# Tx_ckt_1.net
KiCad netlist of a schematic drawn in EAGLE
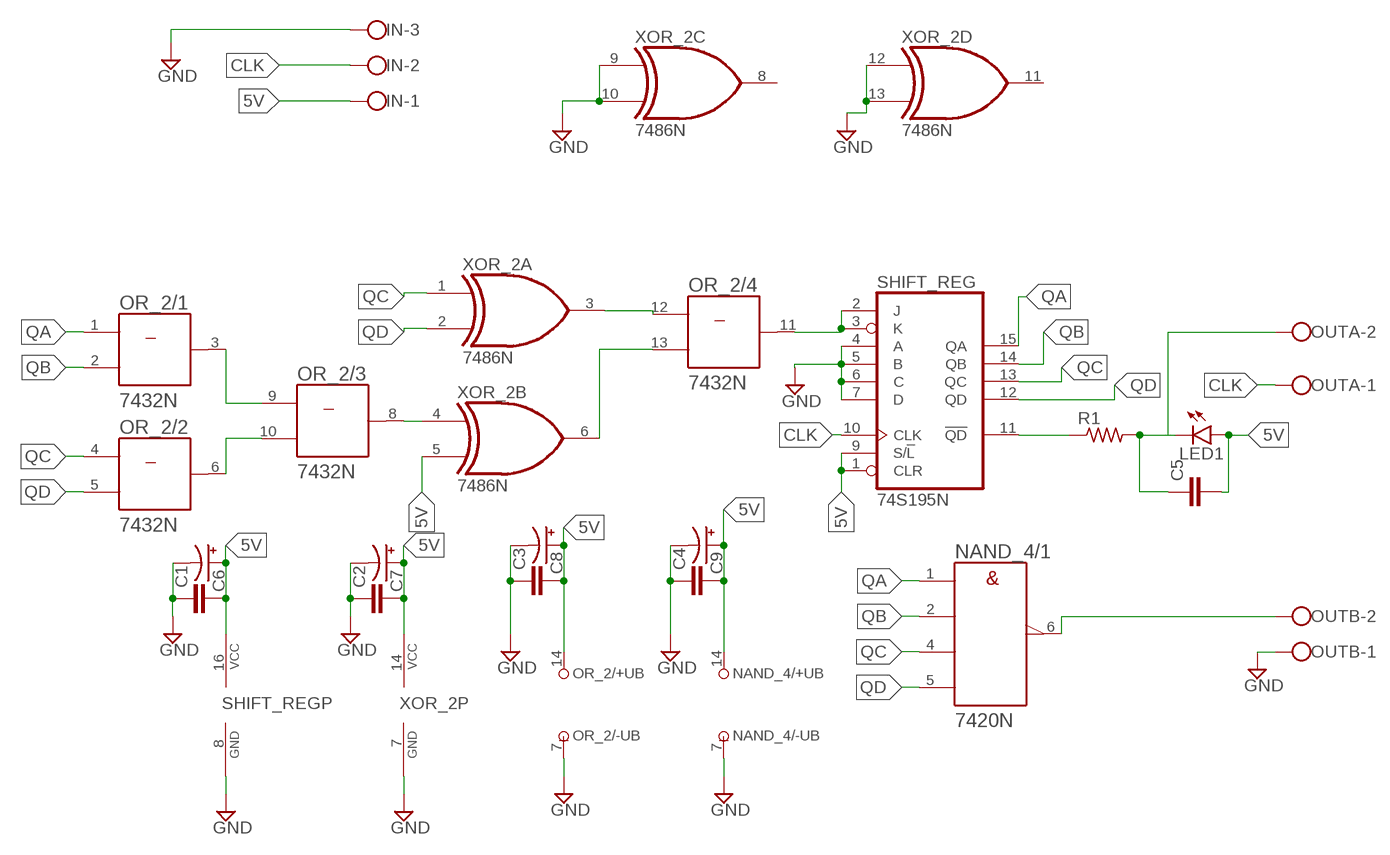
[diagram p0: schematic, sheet 1]

(export (version "E")
  (design (tool "Eeschema 10.0.6"))
  (components
    (comp (ref "C1")
      (value "C-EU050-025X075")
      (footprint "eagle-import:C050-025X075")
      (libsource (lib "eagle-import") (part "C-EU050-025X075"))
    )
    (comp (ref "C2")
      (value "C-EU050-025X075")
      (footprint "eagle-import:C050-025X075")
      (libsource (lib "eagle-import") (part "C-EU050-025X075"))
    )
    (comp (ref "C3")
      (value "C-EU050-025X075")
      (footprint "eagle-import:C050-025X075")
      (libsource (lib "eagle-import") (part "C-EU050-025X075"))
    )
    (comp (ref "C4")
      (value "C-EU050-025X075")
      (footprint "eagle-import:C050-025X075")
      (libsource (lib "eagle-import") (part "C-EU050-025X075"))
    )
    (comp (ref "C5")
      (value "C-EU050-025X075")
      (footprint "eagle-import:C050-025X075")
      (libsource (lib "eagle-import") (part "C-EU050-025X075"))
    )
    (comp (ref "C6")
      (value "CPOL-USE2.5-7")
      (footprint "eagle-import:E2,5-7")
      (libsource (lib "eagle-import") (part "CPOL-USE2.5-7"))
    )
    (comp (ref "C7")
      (value "CPOL-USE2.5-7")
      (footprint "eagle-import:E2,5-7")
      (libsource (lib "eagle-import") (part "CPOL-USE2.5-7"))
    )
    (comp (ref "C8")
      (value "CPOL-USE2.5-7")
      (footprint "eagle-import:E2,5-7")
      (libsource (lib "eagle-import") (part "CPOL-USE2.5-7"))
    )
    (comp (ref "C9")
      (value "CPOL-USE2.5-7")
      (footprint "eagle-import:E2,5-7")
      (libsource (lib "eagle-import") (part "CPOL-USE2.5-7"))
    )
    (comp (ref "IN")
      (value "W237-103")
      (footprint "eagle-import:W237-103")
      (fields (field (name "MPN") "237-103"))
      (libsource (lib "eagle-import") (part "W237-103"))
    )
    (comp (ref "LED1")
      (value "LED5MM")
      (footprint "eagle-import:LED5MM")
      (libsource (lib "eagle-import") (part "LED5MM"))
    )
    (comp (ref "NAND_4")
      (value "7420N")
      (footprint "eagle-import:DIL14")
      (libsource (lib "eagle-import") (part "7420N"))
    )
    (comp (ref "OR_2")
      (value "7432N")
      (footprint "eagle-import:DIL14")
      (libsource (lib "eagle-import") (part "7432N"))
    )
    (comp (ref "OUTA")
      (value "W237-102")
      (footprint "eagle-import:W237-102")
      (fields (field (name "MPN") "237-102"))
      (libsource (lib "eagle-import") (part "W237-102"))
    )
    (comp (ref "OUTB")
      (value "W237-102")
      (footprint "eagle-import:W237-102")
      (fields (field (name "MPN") "237-102"))
      (libsource (lib "eagle-import") (part "W237-102"))
    )
    (comp (ref "R1")
      (value "R-US_0207/10")
      (footprint "eagle-import:0207_10")
      (libsource (lib "eagle-import") (part "R-US_0207/10"))
    )
    (comp (ref "SHIFT_REG")
      (value "74S195N")
      (footprint "eagle-import:DIL16")
      (libsource (lib "eagle-import") (part "74195NS"))
    )
    (comp (ref "XOR_2")
      (value "7486N")
      (footprint "eagle-import:DIL14")
      (libsource (lib "eagle-import") (part "7486N"))
    )
  )
  (nets
    (net (code "1") (name "5V") (class "Default")
      (node (ref "C1") (pin "2") (pinfunction "2_2") (pintype "passive"))
      (node (ref "C2") (pin "2") (pinfunction "2_2") (pintype "passive"))
      (node (ref "C3") (pin "2") (pinfunction "2_2") (pintype "passive"))
      (node (ref "C4") (pin "2") (pinfunction "2_2") (pintype "passive"))
      (node (ref "C5") (pin "2") (pinfunction "2_2") (pintype "passive"))
      (node (ref "C6") (pin "+") (pinfunction "+_+") (pintype "passive"))
      (node (ref "C7") (pin "+") (pinfunction "+_+") (pintype "passive"))
      (node (ref "C8") (pin "+") (pinfunction "+_+") (pintype "passive"))
      (node (ref "C9") (pin "+") (pinfunction "+_+") (pintype "passive"))
      (node (ref "IN") (pin "1") (pinfunction "KL_1") (pintype "passive"))
      (node (ref "LED1") (pin "A") (pinfunction "A_A") (pintype "passive"))
      (node (ref "NAND_4") (pin "14") (pinfunction "+UB_14") (pintype "power_in"))
      (node (ref "OR_2") (pin "14") (pinfunction "+UB_14") (pintype "power_in"))
      (node (ref "SHIFT_REG") (pin "1") (pinfunction "CLR_1") (pintype "input"))
      (node (ref "SHIFT_REG") (pin "16") (pinfunction "VCC_16") (pintype "power_in"))
      (node (ref "SHIFT_REG") (pin "9") (pinfunction "S/~{L}_9") (pintype "input"))
      (node (ref "XOR_2") (pin "14") (pinfunction "VCC_14") (pintype "power_in"))
      (node (ref "XOR_2") (pin "5") (pinfunction "I1_5") (pintype "input"))
    )
    (net (code "2") (name "CLK") (class "Default")
      (node (ref "IN") (pin "2") (pinfunction "KL_2") (pintype "passive"))
      (node (ref "OUTA") (pin "1") (pinfunction "KL_1") (pintype "passive"))
      (node (ref "SHIFT_REG") (pin "10") (pinfunction "CLK_10") (pintype "input"))
    )
    (net (code "3") (name "GND") (class "Default")
      (node (ref "C1") (pin "1") (pinfunction "1_1") (pintype "passive"))
      (node (ref "C2") (pin "1") (pinfunction "1_1") (pintype "passive"))
      (node (ref "C3") (pin "1") (pinfunction "1_1") (pintype "passive"))
      (node (ref "C4") (pin "1") (pinfunction "1_1") (pintype "passive"))
      (node (ref "C6") (pin "-") (pinfunction "-_-") (pintype "passive"))
      (node (ref "C7") (pin "-") (pinfunction "-_-") (pintype "passive"))
      (node (ref "C8") (pin "-") (pinfunction "-_-") (pintype "passive"))
      (node (ref "C9") (pin "-") (pinfunction "-_-") (pintype "passive"))
      (node (ref "IN") (pin "3") (pinfunction "KL_3") (pintype "passive"))
      (node (ref "NAND_4") (pin "7") (pinfunction "-UB_7") (pintype "power_in"))
      (node (ref "OR_2") (pin "7") (pinfunction "-UB_7") (pintype "power_in"))
      (node (ref "OUTB") (pin "1") (pinfunction "KL_1") (pintype "passive"))
      (node (ref "SHIFT_REG") (pin "4") (pinfunction "A_4") (pintype "input"))
      (node (ref "SHIFT_REG") (pin "5") (pinfunction "B_5") (pintype "input"))
      (node (ref "SHIFT_REG") (pin "6") (pinfunction "C_6") (pintype "input"))
      (node (ref "SHIFT_REG") (pin "7") (pinfunction "D_7") (pintype "input"))
      (node (ref "SHIFT_REG") (pin "8") (pinfunction "GND_8") (pintype "power_in"))
      (node (ref "XOR_2") (pin "10") (pinfunction "I1_10") (pintype "input"))
      (node (ref "XOR_2") (pin "12") (pinfunction "I0_12") (pintype "input"))
      (node (ref "XOR_2") (pin "13") (pinfunction "I1_13") (pintype "input"))
      (node (ref "XOR_2") (pin "7") (pinfunction "GND_7") (pintype "power_in"))
      (node (ref "XOR_2") (pin "9") (pinfunction "I0_9") (pintype "input"))
    )
    (net (code "4") (name "Net-(LED1-C)") (class "Default")
      (node (ref "C5") (pin "1") (pinfunction "1_1") (pintype "passive"))
      (node (ref "LED1") (pin "K") (pinfunction "C_K") (pintype "passive"))
      (node (ref "OUTA") (pin "2") (pinfunction "KL_2") (pintype "passive"))
      (node (ref "R1") (pin "2") (pinfunction "2_2") (pintype "passive"))
    )
    (net (code "5") (name "Net-(NAND_4C-Y)") (class "Default")
      (node (ref "NAND_4") (pin "6") (pinfunction "Y_6") (pintype "output"))
      (node (ref "OUTB") (pin "2") (pinfunction "KL_2") (pintype "passive"))
    )
    (net (code "6") (name "Net-(OR_2C-Y)") (class "Default")
      (node (ref "OR_2") (pin "3") (pinfunction "Y_3") (pintype "output"))
      (node (ref "OR_2") (pin "9") (pinfunction "A_9") (pintype "input"))
    )
    (net (code "7") (name "Net-(OR_2D-Y)") (class "Default")
      (node (ref "OR_2") (pin "10") (pinfunction "B_10") (pintype "input"))
      (node (ref "OR_2") (pin "6") (pinfunction "Y_6") (pintype "output"))
    )
    (net (code "8") (name "Net-(OR_2E-Y)") (class "Default")
      (node (ref "OR_2") (pin "8") (pinfunction "Y_8") (pintype "output"))
      (node (ref "XOR_2") (pin "4") (pinfunction "I0_4") (pintype "input"))
    )
    (net (code "9") (name "Net-(OR_2F-A)") (class "Default")
      (node (ref "OR_2") (pin "12") (pinfunction "A_12") (pintype "input"))
      (node (ref "XOR_2") (pin "3") (pinfunction "O_3") (pintype "output"))
    )
    (net (code "10") (name "Net-(OR_2F-B)") (class "Default")
      (node (ref "OR_2") (pin "13") (pinfunction "B_13") (pintype "input"))
      (node (ref "XOR_2") (pin "6") (pinfunction "O_6") (pintype "output"))
    )
    (net (code "11") (name "Net-(OR_2F-Y)") (class "Default")
      (node (ref "OR_2") (pin "11") (pinfunction "Y_11") (pintype "output"))
      (node (ref "SHIFT_REG") (pin "2") (pinfunction "J_2") (pintype "input"))
      (node (ref "SHIFT_REG") (pin "3") (pinfunction "K_3") (pintype "input"))
    )
    (net (code "12") (name "Net-(SHIFT_REGA-~{QD})") (class "Default")
      (node (ref "R1") (pin "1") (pinfunction "1_1") (pintype "passive"))
      (node (ref "SHIFT_REG") (pin "11") (pinfunction "~{QD}_11") (pintype "output"))
    )
    (net (code "13") (name "QA") (class "Default")
      (node (ref "NAND_4") (pin "1") (pinfunction "A_1") (pintype "input"))
      (node (ref "OR_2") (pin "1") (pinfunction "A_1") (pintype "input"))
      (node (ref "SHIFT_REG") (pin "15") (pinfunction "QA_15") (pintype "output"))
    )
    (net (code "14") (name "QB") (class "Default")
      (node (ref "NAND_4") (pin "2") (pinfunction "B_2") (pintype "input"))
      (node (ref "OR_2") (pin "2") (pinfunction "B_2") (pintype "input"))
      (node (ref "SHIFT_REG") (pin "14") (pinfunction "QB_14") (pintype "output"))
    )
    (net (code "15") (name "QC") (class "Default")
      (node (ref "NAND_4") (pin "4") (pinfunction "C_4") (pintype "input"))
      (node (ref "OR_2") (pin "4") (pinfunction "A_4") (pintype "input"))
      (node (ref "SHIFT_REG") (pin "13") (pinfunction "QC_13") (pintype "output"))
      (node (ref "XOR_2") (pin "1") (pinfunction "I0_1") (pintype "input"))
    )
    (net (code "16") (name "QD") (class "Default")
      (node (ref "NAND_4") (pin "5") (pinfunction "D_5") (pintype "input"))
      (node (ref "OR_2") (pin "5") (pinfunction "B_5") (pintype "input"))
      (node (ref "SHIFT_REG") (pin "12") (pinfunction "QD_12") (pintype "output"))
      (node (ref "XOR_2") (pin "2") (pinfunction "I1_2") (pintype "input"))
    )
    (net (code "17") (name "unconnected-(XOR_2C-O-Pad8)") (class "Default")
      (node (ref "XOR_2") (pin "8") (pinfunction "O_8") (pintype "output"))
    )
    (net (code "18") (name "unconnected-(XOR_2D-O-Pad11)") (class "Default")
      (node (ref "XOR_2") (pin "11") (pinfunction "O_11") (pintype "output"))
    )
  )
)
